# Sheet1.net
KiCad netlist of a schematic drawn in Altium Designer
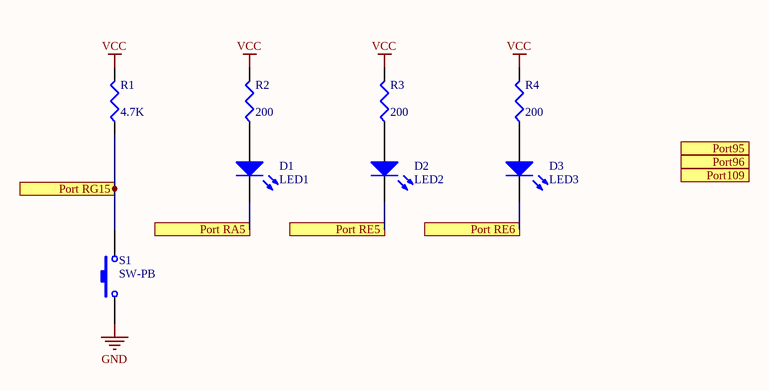
[diagram p0: Sheet1.SchDoc]

(export (version "E")
  (design (tool "Eeschema 10.0.6"))
  (components
    (comp (ref "D1")
      (value "LED1")
      (footprint "LED-1")
      (description "Typical RED GaAs LED")
      (fields (field (name "PUBLISHER") "Altium Limited"))
      (libsource (lib "Miscellaneous Devices") (part "LED1"))
    )
    (comp (ref "D2")
      (value "LED2")
      (footprint "3.2X1.6X1.1")
      (description "Typical RED, GREEN, YELLOW, AMBER GaAs LED")
      (fields (field (name "PUBLISHER") "Altium Limited"))
      (libsource (lib "Miscellaneous Devices") (part "LED2"))
    )
    (comp (ref "D3")
      (value "LED3")
      (footprint "3.5X2.8X1.9")
      (description "Typical BLUE SiC LED")
      (fields (field (name "PUBLISHER") "Altium Limited"))
      (libsource (lib "Miscellaneous Devices") (part "LED3"))
    )
    (comp (ref "R1")
      (value "4.7K")
      (footprint "J1-0603")
      (description "Resistor")
      (fields (field (name "PUBLISHER") "Altium Limited"))
      (libsource (lib "Miscellaneous Devices") (part "Res3"))
    )
    (comp (ref "R2")
      (value "200")
      (footprint "J1-0603")
      (description "Resistor")
      (fields (field (name "PUBLISHER") "Altium Limited"))
      (libsource (lib "Miscellaneous Devices") (part "Res3"))
    )
    (comp (ref "R3")
      (value "200")
      (footprint "J1-0603")
      (description "Resistor")
      (fields (field (name "PUBLISHER") "Altium Limited"))
      (libsource (lib "Miscellaneous Devices") (part "Res3"))
    )
    (comp (ref "R4")
      (value "200")
      (footprint "J1-0603")
      (description "Resistor")
      (fields (field (name "PUBLISHER") "Altium Limited"))
      (libsource (lib "Miscellaneous Devices") (part "Res3"))
    )
    (comp (ref "S1")
      (value "SW-PB")
      (footprint "SPST-2")
      (description "Switch")
      (fields (field (name "PUBLISHER") "Altium Limited"))
      (libsource (lib "Miscellaneous Devices") (part "SW-PB"))
    )
  )
  (nets
    (net (code "1") (name "/Port RA5") (class "Default")
      (node (ref "D1") (pin "2") (pinfunction "K_2") (pintype "passive"))
    )
    (net (code "2") (name "/Port RE5") (class "Default")
      (node (ref "D2") (pin "2") (pinfunction "K_2") (pintype "passive"))
    )
    (net (code "3") (name "/Port RE6") (class "Default")
      (node (ref "D3") (pin "2") (pinfunction "K_2") (pintype "passive"))
    )
    (net (code "4") (name "/Port RG15") (class "Default")
      (node (ref "R1") (pin "1") (pinfunction "1_1") (pintype "passive"))
      (node (ref "S1") (pin "2") (pinfunction "2_2") (pintype "passive"))
    )
    (net (code "8") (name "GND") (class "Default")
      (node (ref "S1") (pin "1") (pinfunction "1_1") (pintype "passive"))
    )
    (net (code "9") (name "Net-(D1-A)") (class "Default")
      (node (ref "D1") (pin "1") (pinfunction "A_1") (pintype "passive"))
      (node (ref "R2") (pin "1") (pinfunction "1_1") (pintype "passive"))
    )
    (net (code "10") (name "Net-(D2-A)") (class "Default")
      (node (ref "D2") (pin "1") (pinfunction "A_1") (pintype "passive"))
      (node (ref "R3") (pin "1") (pinfunction "1_1") (pintype "passive"))
    )
    (net (code "11") (name "Net-(D3-A)") (class "Default")
      (node (ref "D3") (pin "1") (pinfunction "A_1") (pintype "passive"))
      (node (ref "R4") (pin "1") (pinfunction "1_1") (pintype "passive"))
    )
    (net (code "12") (name "VCC") (class "Default")
      (node (ref "R1") (pin "2") (pinfunction "2_2") (pintype "passive"))
      (node (ref "R2") (pin "2") (pinfunction "2_2") (pintype "passive"))
      (node (ref "R3") (pin "2") (pinfunction "2_2") (pintype "passive"))
      (node (ref "R4") (pin "2") (pinfunction "2_2") (pintype "passive"))
    )
  )
)
